# tb_project_ir_blaster_wemos_revA.net
KiCad netlist of a schematic drawn in EAGLE
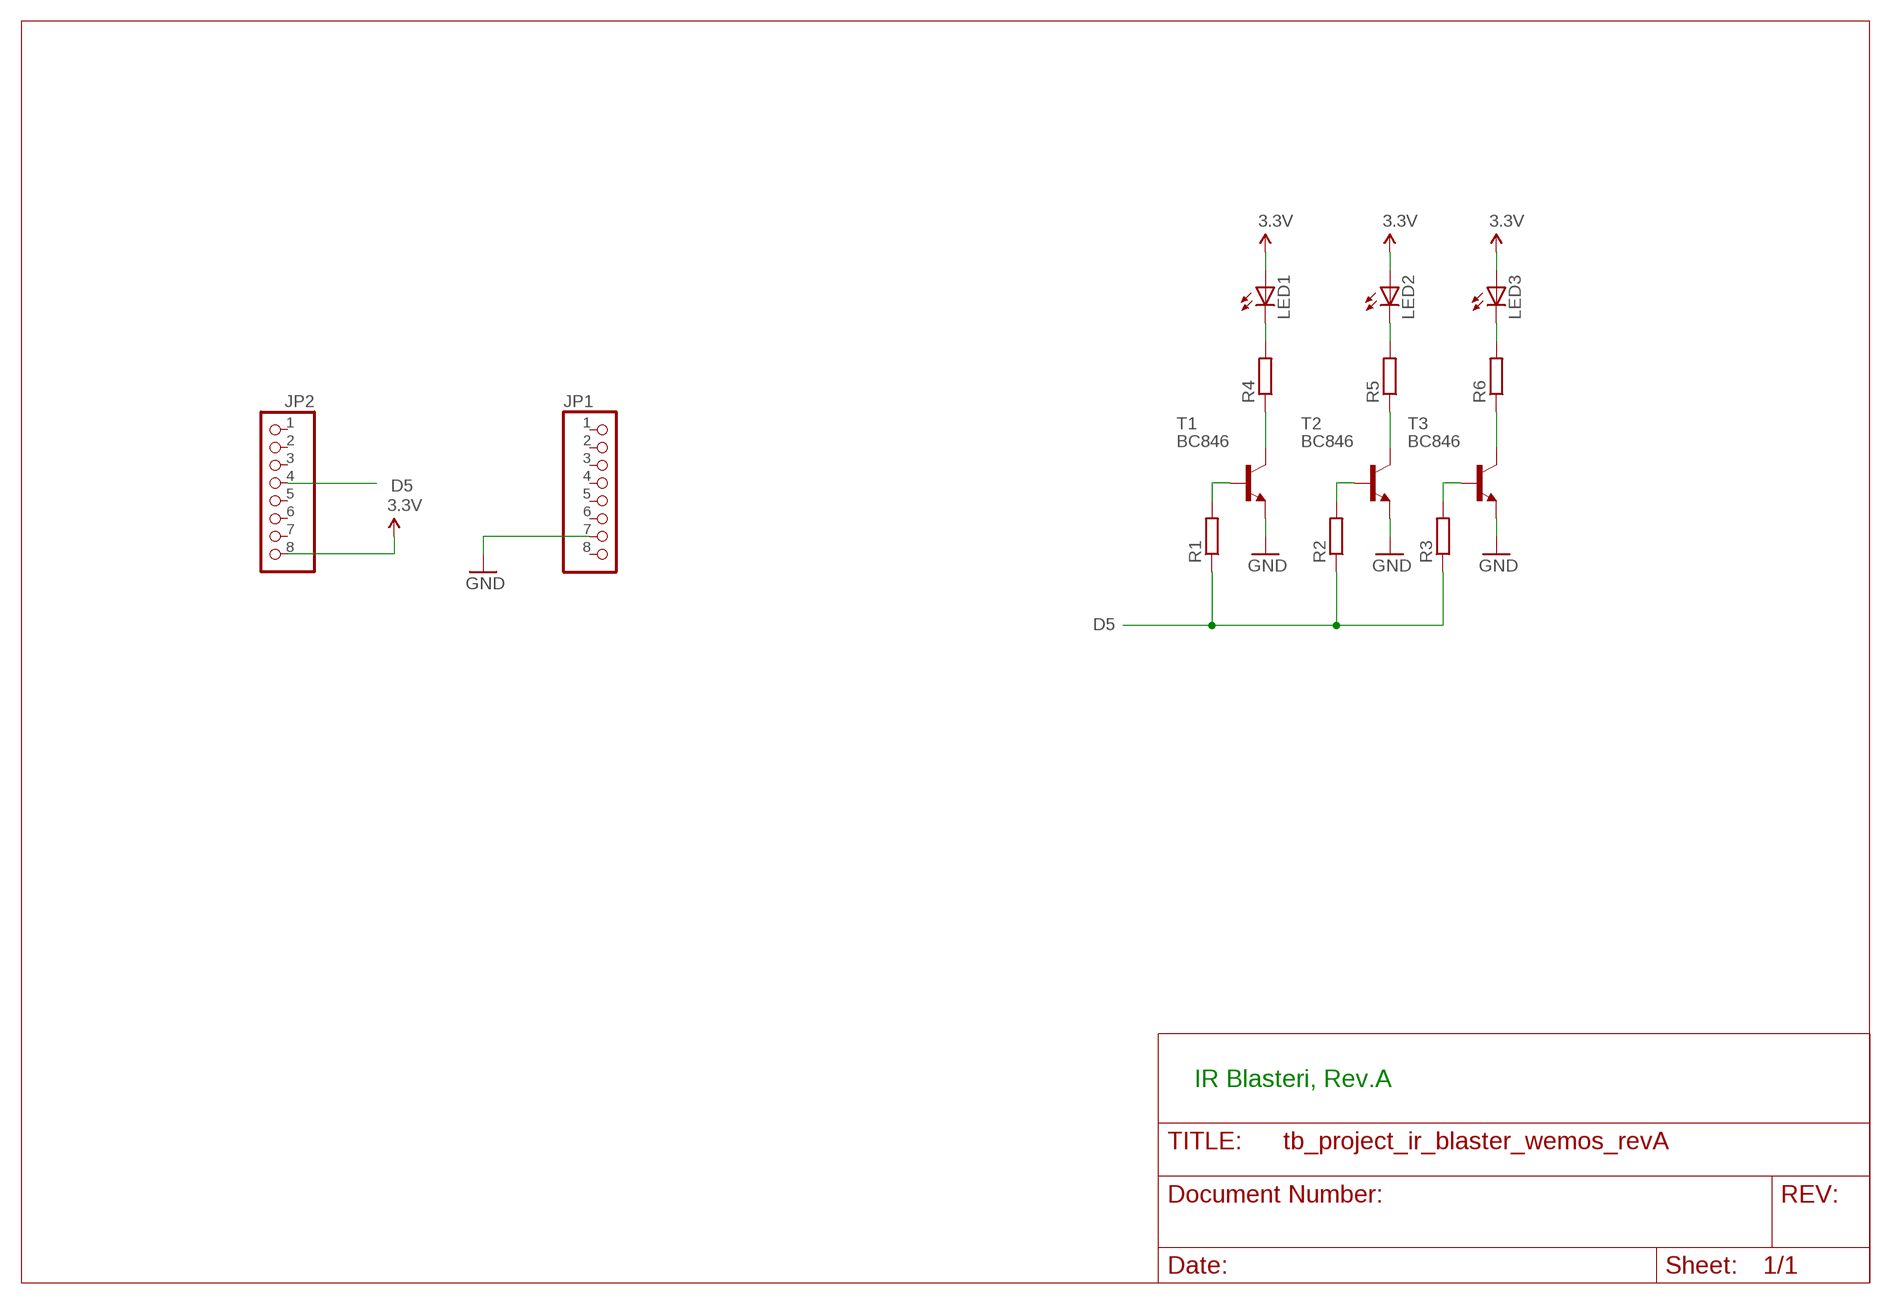
[diagram p0: schematic, sheet 1]

(export (version "E")
  (design (tool "Eeschema 10.0.6"))
  (components
    (comp (ref "JP1")
      (value "PINHD-1X8")
      (footprint "eagle-import:1X08")
      (libsource (lib "eagle-import") (part "PINHD-1X8"))
    )
    (comp (ref "JP2")
      (value "PINHD-1X8")
      (footprint "eagle-import:1X08")
      (libsource (lib "eagle-import") (part "PINHD-1X8"))
    )
    (comp (ref "LED1")
      (value "LED5MM")
      (footprint "eagle-import:LED5MM")
      (libsource (lib "eagle-import") (part "LED5MM"))
    )
    (comp (ref "LED2")
      (value "LED5MM")
      (footprint "eagle-import:LED5MM")
      (libsource (lib "eagle-import") (part "LED5MM"))
    )
    (comp (ref "LED3")
      (value "LED5MM")
      (footprint "eagle-import:LED5MM")
      (libsource (lib "eagle-import") (part "LED5MM"))
    )
    (comp (ref "R1")
      (value "R-EU_R1206")
      (footprint "eagle-import:R1206")
      (libsource (lib "eagle-import") (part "R-EU_R1206"))
    )
    (comp (ref "R2")
      (value "R-EU_R1206")
      (footprint "eagle-import:R1206")
      (libsource (lib "eagle-import") (part "R-EU_R1206"))
    )
    (comp (ref "R3")
      (value "R-EU_R1206")
      (footprint "eagle-import:R1206")
      (libsource (lib "eagle-import") (part "R-EU_R1206"))
    )
    (comp (ref "R4")
      (value "R-EU_R1206")
      (footprint "eagle-import:R1206")
      (libsource (lib "eagle-import") (part "R-EU_R1206"))
    )
    (comp (ref "R5")
      (value "R-EU_R1206")
      (footprint "eagle-import:R1206")
      (libsource (lib "eagle-import") (part "R-EU_R1206"))
    )
    (comp (ref "R6")
      (value "R-EU_R1206")
      (footprint "eagle-import:R1206")
      (libsource (lib "eagle-import") (part "R-EU_R1206"))
    )
    (comp (ref "T1")
      (value "BC846")
      (footprint "eagle-import:SOT23")
      (libsource (lib "eagle-import") (part "BC846"))
    )
    (comp (ref "T2")
      (value "BC846")
      (footprint "eagle-import:SOT23")
      (libsource (lib "eagle-import") (part "BC846"))
    )
    (comp (ref "T3")
      (value "BC846")
      (footprint "eagle-import:SOT23")
      (libsource (lib "eagle-import") (part "BC846"))
    )
  )
  (nets
    (net (code "1") (name "/D5") (class "Default")
      (node (ref "JP2") (pin "4") (pinfunction "4_4") (pintype "passive"))
      (node (ref "R1") (pin "1") (pinfunction "1_1") (pintype "passive"))
      (node (ref "R2") (pin "1") (pinfunction "1_1") (pintype "passive"))
      (node (ref "R3") (pin "1") (pinfunction "1_1") (pintype "passive"))
    )
    (net (code "2") (name "3.3V") (class "Default")
      (node (ref "JP2") (pin "8") (pinfunction "8_8") (pintype "passive"))
      (node (ref "LED1") (pin "A") (pinfunction "A_A") (pintype "passive"))
      (node (ref "LED2") (pin "A") (pinfunction "A_A") (pintype "passive"))
      (node (ref "LED3") (pin "A") (pinfunction "A_A") (pintype "passive"))
    )
    (net (code "3") (name "GND") (class "Default")
      (node (ref "JP1") (pin "7") (pinfunction "7_7") (pintype "passive"))
      (node (ref "T1") (pin "2") (pinfunction "E_2") (pintype "passive"))
      (node (ref "T2") (pin "2") (pinfunction "E_2") (pintype "passive"))
      (node (ref "T3") (pin "2") (pinfunction "E_2") (pintype "passive"))
    )
    (net (code "4") (name "Net-(LED1-C)") (class "Default")
      (node (ref "LED1") (pin "K") (pinfunction "C_K") (pintype "passive"))
      (node (ref "R4") (pin "2") (pinfunction "2_2") (pintype "passive"))
    )
    (net (code "5") (name "Net-(LED2-C)") (class "Default")
      (node (ref "LED2") (pin "K") (pinfunction "C_K") (pintype "passive"))
      (node (ref "R5") (pin "2") (pinfunction "2_2") (pintype "passive"))
    )
    (net (code "6") (name "Net-(LED3-C)") (class "Default")
      (node (ref "LED3") (pin "K") (pinfunction "C_K") (pintype "passive"))
      (node (ref "R6") (pin "2") (pinfunction "2_2") (pintype "passive"))
    )
    (net (code "7") (name "Net-(T1-B)") (class "Default")
      (node (ref "R1") (pin "2") (pinfunction "2_2") (pintype "passive"))
      (node (ref "T1") (pin "1") (pinfunction "B_1") (pintype "passive"))
    )
    (net (code "8") (name "Net-(T1-C)") (class "Default")
      (node (ref "R4") (pin "1") (pinfunction "1_1") (pintype "passive"))
      (node (ref "T1") (pin "3") (pinfunction "C_3") (pintype "passive"))
    )
    (net (code "9") (name "Net-(T2-B)") (class "Default")
      (node (ref "R2") (pin "2") (pinfunction "2_2") (pintype "passive"))
      (node (ref "T2") (pin "1") (pinfunction "B_1") (pintype "passive"))
    )
    (net (code "10") (name "Net-(T2-C)") (class "Default")
      (node (ref "R5") (pin "1") (pinfunction "1_1") (pintype "passive"))
      (node (ref "T2") (pin "3") (pinfunction "C_3") (pintype "passive"))
    )
    (net (code "11") (name "Net-(T3-B)") (class "Default")
      (node (ref "R3") (pin "2") (pinfunction "2_2") (pintype "passive"))
      (node (ref "T3") (pin "1") (pinfunction "B_1") (pintype "passive"))
    )
    (net (code "12") (name "Net-(T3-C)") (class "Default")
      (node (ref "R6") (pin "1") (pinfunction "1_1") (pintype "passive"))
      (node (ref "T3") (pin "3") (pinfunction "C_3") (pintype "passive"))
    )
    (net (code "13") (name "unconnected-(JP1-Pad1)") (class "Default")
      (node (ref "JP1") (pin "1") (pinfunction "1_1") (pintype "passive"))
    )
    (net (code "14") (name "unconnected-(JP1-Pad2)") (class "Default")
      (node (ref "JP1") (pin "2") (pinfunction "2_2") (pintype "passive"))
    )
    (net (code "15") (name "unconnected-(JP1-Pad3)") (class "Default")
      (node (ref "JP1") (pin "3") (pinfunction "3_3") (pintype "passive"))
    )
    (net (code "16") (name "unconnected-(JP1-Pad4)") (class "Default")
      (node (ref "JP1") (pin "4") (pinfunction "4_4") (pintype "passive"))
    )
    (net (code "17") (name "unconnected-(JP1-Pad5)") (class "Default")
      (node (ref "JP1") (pin "5") (pinfunction "5_5") (pintype "passive"))
    )
    (net (code "18") (name "unconnected-(JP1-Pad6)") (class "Default")
      (node (ref "JP1") (pin "6") (pinfunction "6_6") (pintype "passive"))
    )
    (net (code "19") (name "unconnected-(JP1-Pad8)") (class "Default")
      (node (ref "JP1") (pin "8") (pinfunction "8_8") (pintype "passive"))
    )
    (net (code "20") (name "unconnected-(JP2-Pad1)") (class "Default")
      (node (ref "JP2") (pin "1") (pinfunction "1_1") (pintype "passive"))
    )
    (net (code "21") (name "unconnected-(JP2-Pad2)") (class "Default")
      (node (ref "JP2") (pin "2") (pinfunction "2_2") (pintype "passive"))
    )
    (net (code "22") (name "unconnected-(JP2-Pad3)") (class "Default")
      (node (ref "JP2") (pin "3") (pinfunction "3_3") (pintype "passive"))
    )
    (net (code "23") (name "unconnected-(JP2-Pad5)") (class "Default")
      (node (ref "JP2") (pin "5") (pinfunction "5_5") (pintype "passive"))
    )
    (net (code "24") (name "unconnected-(JP2-Pad6)") (class "Default")
      (node (ref "JP2") (pin "6") (pinfunction "6_6") (pintype "passive"))
    )
    (net (code "25") (name "unconnected-(JP2-Pad7)") (class "Default")
      (node (ref "JP2") (pin "7") (pinfunction "7_7") (pintype "passive"))
    )
  )
)
